# obc.net
KiCad netlist of a schematic drawn in EAGLE
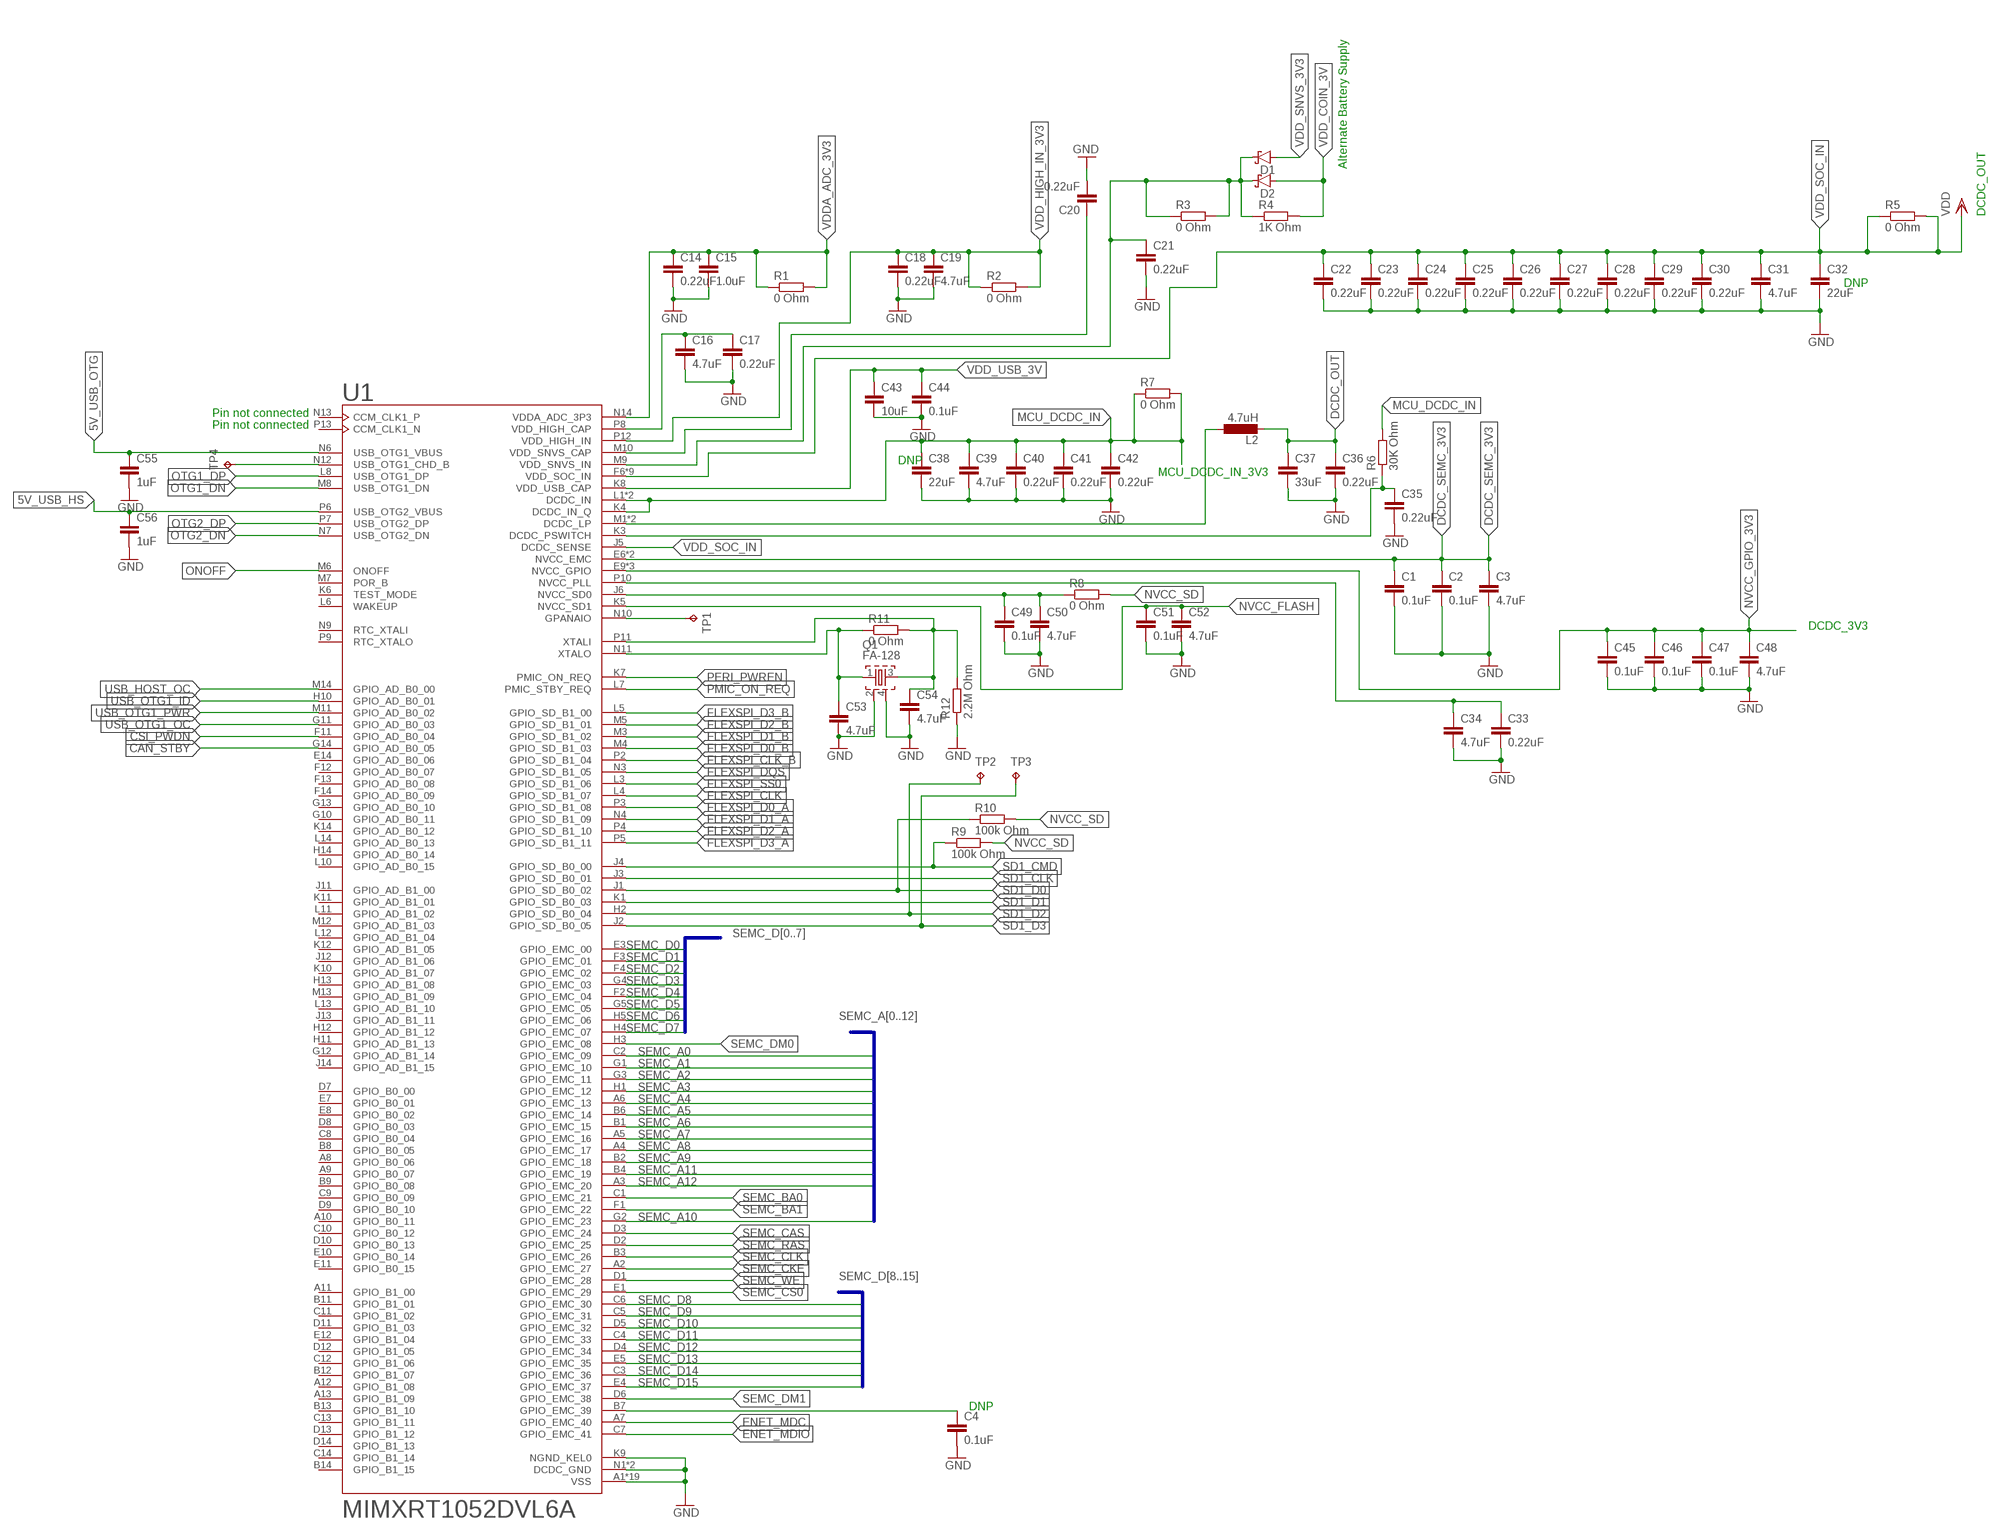
[diagram p0: schematic, sheet 1]
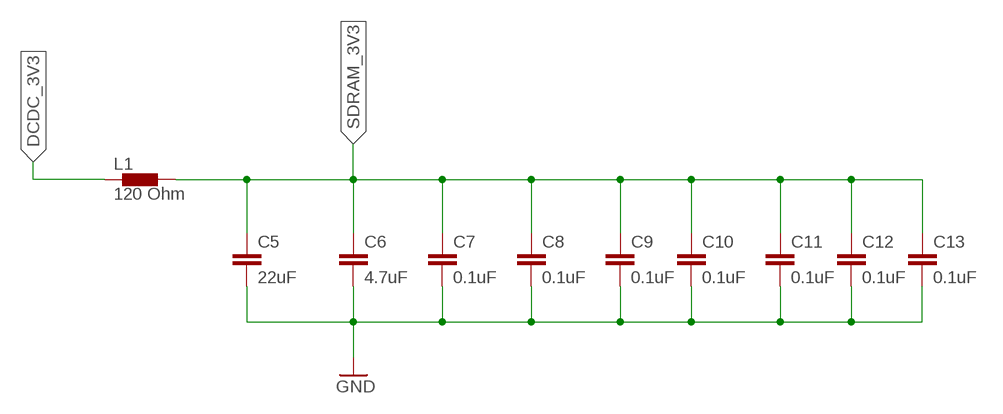
[diagram p1: schematic, sheet 2]

(export (version "E")
  (design (tool "Eeschema 10.0.6"))
  (components
    (comp (ref "C5")
      (value "22uF")
      (footprint "eagle-import:C0402K")
      (libsource (lib "eagle-import") (part "C-EUC0402K"))
    )
    (comp (ref "C6")
      (value "4.7uF")
      (footprint "eagle-import:C0402K")
      (libsource (lib "eagle-import") (part "C-EUC0402K"))
    )
    (comp (ref "C7")
      (value "0.1uF")
      (footprint "eagle-import:C0402K")
      (libsource (lib "eagle-import") (part "C-EUC0402K"))
    )
    (comp (ref "C8")
      (value "0.1uF")
      (footprint "eagle-import:C0402K")
      (libsource (lib "eagle-import") (part "C-EUC0402K"))
    )
    (comp (ref "C9")
      (value "0.1uF")
      (footprint "eagle-import:C0402K")
      (libsource (lib "eagle-import") (part "C-EUC0402K"))
    )
    (comp (ref "C10")
      (value "0.1uF")
      (footprint "eagle-import:C0402K")
      (libsource (lib "eagle-import") (part "C-EUC0402K"))
    )
    (comp (ref "C11")
      (value "0.1uF")
      (footprint "eagle-import:C0402K")
      (libsource (lib "eagle-import") (part "C-EUC0402K"))
    )
    (comp (ref "C12")
      (value "0.1uF")
      (footprint "eagle-import:C0402K")
      (libsource (lib "eagle-import") (part "C-EUC0402K"))
    )
    (comp (ref "C13")
      (value "0.1uF")
      (footprint "eagle-import:C0402K")
      (libsource (lib "eagle-import") (part "C-EUC0402K"))
    )
    (comp (ref "L1")
      (value "120 Ohm")
      (footprint "eagle-import:0402")
      (libsource (lib "eagle-import") (part "BLM15HB121SN1"))
    )
    (comp (ref "C1")
      (value "0.1uF")
      (footprint "eagle-import:C0402K")
      (libsource (lib "eagle-import") (part "C-EUC0402K"))
    )
    (comp (ref "C2")
      (value "0.1uF")
      (footprint "eagle-import:C0402K")
      (libsource (lib "eagle-import") (part "C-EUC0402K"))
    )
    (comp (ref "C3")
      (value "4.7uF")
      (footprint "eagle-import:C0402K")
      (libsource (lib "eagle-import") (part "C-EUC0402K"))
    )
    (comp (ref "C4")
      (value "0.1uF")
      (footprint "eagle-import:C0402K")
      (libsource (lib "eagle-import") (part "C-EUC0402K"))
    )
    (comp (ref "C14")
      (value "0.22uF")
      (footprint "eagle-import:C0402K")
      (libsource (lib "eagle-import") (part "C-EUC0402K"))
    )
    (comp (ref "C15")
      (value "1.0uF")
      (footprint "eagle-import:C0402K")
      (libsource (lib "eagle-import") (part "C-EUC0402K"))
    )
    (comp (ref "C16")
      (value "4.7uF")
      (footprint "eagle-import:C0402K")
      (libsource (lib "eagle-import") (part "C-EUC0402K"))
    )
    (comp (ref "C17")
      (value "0.22uF")
      (footprint "eagle-import:C0402K")
      (libsource (lib "eagle-import") (part "C-EUC0402K"))
    )
    (comp (ref "C18")
      (value "0.22uF")
      (footprint "eagle-import:C0402K")
      (libsource (lib "eagle-import") (part "C-EUC0402K"))
    )
    (comp (ref "C19")
      (value "4.7uF")
      (footprint "eagle-import:C0402K")
      (libsource (lib "eagle-import") (part "C-EUC0402K"))
    )
    (comp (ref "C20")
      (value "0.22uF")
      (footprint "eagle-import:C0402K")
      (libsource (lib "eagle-import") (part "C-EUC0402K"))
    )
    (comp (ref "C21")
      (value "0.22uF")
      (footprint "eagle-import:C0402K")
      (libsource (lib "eagle-import") (part "C-EUC0402K"))
    )
    (comp (ref "C22")
      (value "0.22uF")
      (footprint "eagle-import:C0402K")
      (libsource (lib "eagle-import") (part "C-EUC0402K"))
    )
    (comp (ref "C23")
      (value "0.22uF")
      (footprint "eagle-import:C0402K")
      (libsource (lib "eagle-import") (part "C-EUC0402K"))
    )
    (comp (ref "C24")
      (value "0.22uF")
      (footprint "eagle-import:C0402K")
      (libsource (lib "eagle-import") (part "C-EUC0402K"))
    )
    (comp (ref "C25")
      (value "0.22uF")
      (footprint "eagle-import:C0402K")
      (libsource (lib "eagle-import") (part "C-EUC0402K"))
    )
    (comp (ref "C26")
      (value "0.22uF")
      (footprint "eagle-import:C0402K")
      (libsource (lib "eagle-import") (part "C-EUC0402K"))
    )
    (comp (ref "C27")
      (value "0.22uF")
      (footprint "eagle-import:C0402K")
      (libsource (lib "eagle-import") (part "C-EUC0402K"))
    )
    (comp (ref "C28")
      (value "0.22uF")
      (footprint "eagle-import:C0402K")
      (libsource (lib "eagle-import") (part "C-EUC0402K"))
    )
    (comp (ref "C29")
      (value "0.22uF")
      (footprint "eagle-import:C0402K")
      (libsource (lib "eagle-import") (part "C-EUC0402K"))
    )
    (comp (ref "C30")
      (value "0.22uF")
      (footprint "eagle-import:C0402K")
      (libsource (lib "eagle-import") (part "C-EUC0402K"))
    )
    (comp (ref "C31")
      (value "4.7uF")
      (footprint "eagle-import:C0402K")
      (libsource (lib "eagle-import") (part "C-EUC0402K"))
    )
    (comp (ref "C32")
      (value "22uF")
      (footprint "eagle-import:C0603K")
      (libsource (lib "eagle-import") (part "C-EUC0603K"))
    )
    (comp (ref "C33")
      (value "0.22uF")
      (footprint "eagle-import:C0402K")
      (libsource (lib "eagle-import") (part "C-EUC0402K"))
    )
    (comp (ref "C34")
      (value "4.7uF")
      (footprint "eagle-import:C0402K")
      (libsource (lib "eagle-import") (part "C-EUC0402K"))
    )
    (comp (ref "C35")
      (value "0.22uF")
      (footprint "eagle-import:C0402K")
      (libsource (lib "eagle-import") (part "C-EUC0402K"))
    )
    (comp (ref "C36")
      (value "0.22uF")
      (footprint "eagle-import:C0402K")
      (libsource (lib "eagle-import") (part "C-EUC0402K"))
    )
    (comp (ref "C37")
      (value "33uF")
      (footprint "eagle-import:C0402K")
      (libsource (lib "eagle-import") (part "C-EUC0402K"))
    )
    (comp (ref "C38")
      (value "22uF")
      (footprint "eagle-import:C0402K")
      (libsource (lib "eagle-import") (part "C-EUC0402K"))
    )
    (comp (ref "C39")
      (value "4.7uF")
      (footprint "eagle-import:C0402K")
      (libsource (lib "eagle-import") (part "C-EUC0402K"))
    )
    (comp (ref "C40")
      (value "0.22uF")
      (footprint "eagle-import:C0402K")
      (libsource (lib "eagle-import") (part "C-EUC0402K"))
    )
    (comp (ref "C41")
      (value "0.22uF")
      (footprint "eagle-import:C0402K")
      (libsource (lib "eagle-import") (part "C-EUC0402K"))
    )
    (comp (ref "C42")
      (value "0.22uF")
      (footprint "eagle-import:C0402K")
      (libsource (lib "eagle-import") (part "C-EUC0402K"))
    )
    (comp (ref "C43")
      (value "10uF")
      (footprint "eagle-import:C0402K")
      (libsource (lib "eagle-import") (part "C-EUC0402K"))
    )
    (comp (ref "C44")
      (value "0.1uF")
      (footprint "eagle-import:C0402K")
      (libsource (lib "eagle-import") (part "C-EUC0402K"))
    )
    (comp (ref "C45")
      (value "0.1uF")
      (footprint "eagle-import:C0402K")
      (libsource (lib "eagle-import") (part "C-EUC0402K"))
    )
    (comp (ref "C46")
      (value "0.1uF")
      (footprint "eagle-import:C0402K")
      (libsource (lib "eagle-import") (part "C-EUC0402K"))
    )
    (comp (ref "C47")
      (value "0.1uF")
      (footprint "eagle-import:C0402K")
      (libsource (lib "eagle-import") (part "C-EUC0402K"))
    )
    (comp (ref "C48")
      (value "4.7uF")
      (footprint "eagle-import:C0402K")
      (libsource (lib "eagle-import") (part "C-EUC0402K"))
    )
    (comp (ref "C49")
      (value "0.1uF")
      (footprint "eagle-import:C0402K")
      (libsource (lib "eagle-import") (part "C-EUC0402K"))
    )
    (comp (ref "C50")
      (value "4.7uF")
      (footprint "eagle-import:C0402K")
      (libsource (lib "eagle-import") (part "C-EUC0402K"))
    )
    (comp (ref "C51")
      (value "0.1uF")
      (footprint "eagle-import:C0402K")
      (libsource (lib "eagle-import") (part "C-EUC0402K"))
    )
    (comp (ref "C52")
      (value "4.7uF")
      (footprint "eagle-import:C0402K")
      (libsource (lib "eagle-import") (part "C-EUC0402K"))
    )
    (comp (ref "C53")
      (value "4.7uF")
      (footprint "eagle-import:C0402K")
      (libsource (lib "eagle-import") (part "C-EUC0402K"))
    )
    (comp (ref "C54")
      (value "4.7uF")
      (footprint "eagle-import:C0402K")
      (libsource (lib "eagle-import") (part "C-EUC0402K"))
    )
    (comp (ref "C55")
      (value "1uF")
      (footprint "eagle-import:C0402K")
      (libsource (lib "eagle-import") (part "C-EUC0402K"))
    )
    (comp (ref "C56")
      (value "1uF")
      (footprint "eagle-import:C0402K")
      (libsource (lib "eagle-import") (part "C-EUC0402K"))
    )
    (comp (ref "D1")
      (value "SCHOTTKY-DIODESMC")
      (footprint "eagle-import:SMC")
      (libsource (lib "eagle-import") (part "SCHOTTKY-DIODESMC"))
    )
    (comp (ref "D2")
      (value "SCHOTTKY-DIODESMC")
      (footprint "eagle-import:SMC")
      (libsource (lib "eagle-import") (part "SCHOTTKY-DIODESMC"))
    )
    (comp (ref "L2")
      (value "4.7uH")
      (footprint "eagle-import:L4035M")
      (libsource (lib "eagle-import") (part "L-EUL4035M"))
    )
    (comp (ref "Q1")
      (value "FA-128")
      (footprint "eagle-import:FA-128")
      (libsource (lib "eagle-import") (part "FA-128"))
    )
    (comp (ref "R1")
      (value "0 Ohm")
      (footprint "eagle-import:R0402")
      (libsource (lib "eagle-import") (part "R-EU_R0402"))
    )
    (comp (ref "R2")
      (value "0 Ohm")
      (footprint "eagle-import:R0402")
      (libsource (lib "eagle-import") (part "R-EU_R0402"))
    )
    (comp (ref "R3")
      (value "0 Ohm")
      (footprint "eagle-import:R0402")
      (libsource (lib "eagle-import") (part "R-EU_R0402"))
    )
    (comp (ref "R4")
      (value "1K Ohm")
      (footprint "eagle-import:R0402")
      (libsource (lib "eagle-import") (part "R-EU_R0402"))
    )
    (comp (ref "R5")
      (value "0 Ohm")
      (footprint "eagle-import:R0402")
      (libsource (lib "eagle-import") (part "R-EU_R0402"))
    )
    (comp (ref "R6")
      (value "30K Ohm")
      (footprint "eagle-import:R0402")
      (libsource (lib "eagle-import") (part "R-EU_R0402"))
    )
    (comp (ref "R7")
      (value "0 Ohm")
      (footprint "eagle-import:R0402")
      (libsource (lib "eagle-import") (part "R-EU_R0402"))
    )
    (comp (ref "R8")
      (value "0 Ohm")
      (footprint "eagle-import:R0402")
      (libsource (lib "eagle-import") (part "R-EU_R0402"))
    )
    (comp (ref "R9")
      (value "100k Ohm")
      (footprint "eagle-import:R0402")
      (libsource (lib "eagle-import") (part "R-EU_R0402"))
    )
    (comp (ref "R10")
      (value "100k Ohm")
      (footprint "eagle-import:R0402")
      (libsource (lib "eagle-import") (part "R-EU_R0402"))
    )
    (comp (ref "R11")
      (value "0 Ohm")
      (footprint "eagle-import:R0402")
      (libsource (lib "eagle-import") (part "R-EU_R0402"))
    )
    (comp (ref "R12")
      (value "2.2M Ohm")
      (footprint "eagle-import:R0402")
      (libsource (lib "eagle-import") (part "R-EU_R0402"))
    )
    (comp (ref "TP1")
      (value "TPTP06R")
      (footprint "eagle-import:TP06R")
      (libsource (lib "eagle-import") (part "TPTP06R"))
    )
    (comp (ref "TP2")
      (value "TPTP06R")
      (footprint "eagle-import:TP06R")
      (libsource (lib "eagle-import") (part "TPTP06R"))
    )
    (comp (ref "TP3")
      (value "TPTP06R")
      (footprint "eagle-import:TP06R")
      (libsource (lib "eagle-import") (part "TPTP06R"))
    )
    (comp (ref "TP4")
      (value "TPTP06R")
      (footprint "eagle-import:TP06R")
      (libsource (lib "eagle-import") (part "TPTP06R"))
    )
    (comp (ref "U1")
      (value "MIMXRT1052DVL6A")
      (footprint "eagle-import:BGA196C65P14X14_1000X1000X152N")
      (fields (field (name "DIGI-KEY_PART_NUMBER") "568-13515-ND") (field (name "MF") "NXP USA"))
      (libsource (lib "eagle-import") (part "MIMXRT1052DVL6A"))
    )
  )
  (nets
    (net (code "4") (name "5V_USB_HS") (class "Default")
      (node (ref "C56") (pin "1") (pinfunction "1_1") (pintype "passive"))
      (node (ref "U1") (pin "P6") (pinfunction "USB_OTG2_VBUS_P6") (pintype "bidirectional"))
    )
    (net (code "5") (name "5V_USB_OTG") (class "Default")
      (node (ref "C55") (pin "1") (pinfunction "1_1") (pintype "passive"))
      (node (ref "U1") (pin "N6") (pinfunction "USB_OTG1_VBUS_N6") (pintype "bidirectional"))
    )
    (net (code "6") (name "CAN_STBY") (class "Default")
      (node (ref "U1") (pin "G14") (pinfunction "GPIO_AD_B0_05_G14") (pintype "bidirectional"))
    )
    (net (code "7") (name "CSI_PWDN") (class "Default")
      (node (ref "U1") (pin "F11") (pinfunction "GPIO_AD_B0_04_F11") (pintype "bidirectional"))
    )
    (net (code "8") (name "DCDC_3V3") (class "Default")
      (node (ref "L1") (pin "1") (pinfunction "1_1") (pintype "passive"))
    )
    (net (code "9") (name "DCDC_OUT") (class "Default")
      (node (ref "C36") (pin "1") (pinfunction "1_1") (pintype "passive"))
      (node (ref "C37") (pin "1") (pinfunction "1_1") (pintype "passive"))
      (node (ref "L2") (pin "2") (pinfunction "2_2") (pintype "passive"))
    )
    (net (code "10") (name "DCDC_SEMC_3V3") (class "Default")
      (node (ref "C1") (pin "1") (pinfunction "1_1") (pintype "passive"))
      (node (ref "C2") (pin "1") (pinfunction "1_1") (pintype "passive"))
      (node (ref "C3") (pin "1") (pinfunction "1_1") (pintype "passive"))
      (node (ref "U1") (pin "E6") (pinfunction "NVCC_EMC_E6") (pintype "power_in"))
      (node (ref "U1") (pin "F5") (pinfunction "NVCC_EMC_F5") (pintype "power_in"))
    )
    (net (code "11") (name "ENET_MDC") (class "Default")
      (node (ref "U1") (pin "A7") (pinfunction "GPIO_EMC_40_A7") (pintype "bidirectional"))
    )
    (net (code "12") (name "ENET_MDIO") (class "Default")
      (node (ref "U1") (pin "C7") (pinfunction "GPIO_EMC_41_C7") (pintype "bidirectional"))
    )
    (net (code "13") (name "FLEXSPI_CLK") (class "Default")
      (node (ref "U1") (pin "L4") (pinfunction "GPIO_SD_B1_07_L4") (pintype "bidirectional"))
    )
    (net (code "14") (name "FLEXSPI_CLK_B") (class "Default")
      (node (ref "U1") (pin "P2") (pinfunction "GPIO_SD_B1_04_P2") (pintype "bidirectional"))
    )
    (net (code "15") (name "FLEXSPI_D0_A") (class "Default")
      (node (ref "U1") (pin "P3") (pinfunction "GPIO_SD_B1_08_P3") (pintype "bidirectional"))
    )
    (net (code "16") (name "FLEXSPI_D0_B") (class "Default")
      (node (ref "U1") (pin "M4") (pinfunction "GPIO_SD_B1_03_M4") (pintype "bidirectional"))
    )
    (net (code "17") (name "FLEXSPI_D1_A") (class "Default")
      (node (ref "U1") (pin "N4") (pinfunction "GPIO_SD_B1_09_N4") (pintype "bidirectional"))
    )
    (net (code "18") (name "FLEXSPI_D1_B") (class "Default")
      (node (ref "U1") (pin "M3") (pinfunction "GPIO_SD_B1_02_M3") (pintype "bidirectional"))
    )
    (net (code "19") (name "FLEXSPI_D2_A") (class "Default")
      (node (ref "U1") (pin "P4") (pinfunction "GPIO_SD_B1_10_P4") (pintype "bidirectional"))
    )
    (net (code "20") (name "FLEXSPI_D2_B") (class "Default")
      (node (ref "U1") (pin "M5") (pinfunction "GPIO_SD_B1_01_M5") (pintype "bidirectional"))
    )
    (net (code "21") (name "FLEXSPI_D3_A") (class "Default")
      (node (ref "U1") (pin "P5") (pinfunction "GPIO_SD_B1_11_P5") (pintype "bidirectional"))
    )
    (net (code "22") (name "FLEXSPI_D3_B") (class "Default")
      (node (ref "U1") (pin "L5") (pinfunction "GPIO_SD_B1_00_L5") (pintype "bidirectional"))
    )
    (net (code "23") (name "FLEXSPI_DQS") (class "Default")
      (node (ref "U1") (pin "N3") (pinfunction "GPIO_SD_B1_05_N3") (pintype "bidirectional"))
    )
    (net (code "24") (name "FLEXSPI_SS0") (class "Default")
      (node (ref "U1") (pin "L3") (pinfunction "GPIO_SD_B1_06_L3") (pintype "bidirectional"))
    )
    (net (code "25") (name "GND") (class "Default")
      (node (ref "C1") (pin "2") (pinfunction "2_2") (pintype "passive"))
      (node (ref "C10") (pin "2") (pinfunction "2_2") (pintype "passive"))
      (node (ref "C11") (pin "2") (pinfunction "2_2") (pintype "passive"))
      (node (ref "C12") (pin "2") (pinfunction "2_2") (pintype "passive"))
      (node (ref "C13") (pin "2") (pinfunction "2_2") (pintype "passive"))
      (node (ref "C14") (pin "2") (pinfunction "2_2") (pintype "passive"))
      (node (ref "C15") (pin "2") (pinfunction "2_2") (pintype "passive"))
      (node (ref "C16") (pin "2") (pinfunction "2_2") (pintype "passive"))
      (node (ref "C17") (pin "2") (pinfunction "2_2") (pintype "passive"))
      (node (ref "C18") (pin "2") (pinfunction "2_2") (pintype "passive"))
      (node (ref "C19") (pin "2") (pinfunction "2_2") (pintype "passive"))
      (node (ref "C2") (pin "2") (pinfunction "2_2") (pintype "passive"))
      (node (ref "C20") (pin "2") (pinfunction "2_2") (pintype "passive"))
      (node (ref "C21") (pin "2") (pinfunction "2_2") (pintype "passive"))
      (node (ref "C22") (pin "2") (pinfunction "2_2") (pintype "passive"))
      (node (ref "C23") (pin "2") (pinfunction "2_2") (pintype "passive"))
      (node (ref "C24") (pin "2") (pinfunction "2_2") (pintype "passive"))
      (node (ref "C25") (pin "2") (pinfunction "2_2") (pintype "passive"))
      (node (ref "C26") (pin "2") (pinfunction "2_2") (pintype "passive"))
      (node (ref "C27") (pin "2") (pinfunction "2_2") (pintype "passive"))
      (node (ref "C28") (pin "2") (pinfunction "2_2") (pintype "passive"))
      (node (ref "C29") (pin "2") (pinfunction "2_2") (pintype "passive"))
      (node (ref "C3") (pin "2") (pinfunction "2_2") (pintype "passive"))
      (node (ref "C30") (pin "2") (pinfunction "2_2") (pintype "passive"))
      (node (ref "C31") (pin "2") (pinfunction "2_2") (pintype "passive"))
      (node (ref "C32") (pin "2") (pinfunction "2_2") (pintype "passive"))
      (node (ref "C33") (pin "2") (pinfunction "2_2") (pintype "passive"))
      (node (ref "C34") (pin "2") (pinfunction "2_2") (pintype "passive"))
      (node (ref "C35") (pin "2") (pinfunction "2_2") (pintype "passive"))
      (node (ref "C36") (pin "2") (pinfunction "2_2") (pintype "passive"))
      (node (ref "C37") (pin "2") (pinfunction "2_2") (pintype "passive"))
      (node (ref "C38") (pin "2") (pinfunction "2_2") (pintype "passive"))
      (node (ref "C39") (pin "2") (pinfunction "2_2") (pintype "passive"))
      (node (ref "C4") (pin "2") (pinfunction "2_2") (pintype "passive"))
      (node (ref "C40") (pin "2") (pinfunction "2_2") (pintype "passive"))
      (node (ref "C41") (pin "2") (pinfunction "2_2") (pintype "passive"))
      (node (ref "C42") (pin "2") (pinfunction "2_2") (pintype "passive"))
      (node (ref "C43") (pin "2") (pinfunction "2_2") (pintype "passive"))
      (node (ref "C44") (pin "2") (pinfunction "2_2") (pintype "passive"))
      (node (ref "C45") (pin "2") (pinfunction "2_2") (pintype "passive"))
      (node (ref "C46") (pin "2") (pinfunction "2_2") (pintype "passive"))
      (node (ref "C47") (pin "2") (pinfunction "2_2") (pintype "passive"))
      (node (ref "C48") (pin "2") (pinfunction "2_2") (pintype "passive"))
      (node (ref "C49") (pin "2") (pinfunction "2_2") (pintype "passive"))
      (node (ref "C5") (pin "2") (pinfunction "2_2") (pintype "passive"))
      (node (ref "C50") (pin "2") (pinfunction "2_2") (pintype "passive"))
      (node (ref "C51") (pin "2") (pinfunction "2_2") (pintype "passive"))
      (node (ref "C52") (pin "2") (pinfunction "2_2") (pintype "passive"))
      (node (ref "C53") (pin "2") (pinfunction "2_2") (pintype "passive"))
      (node (ref "C54") (pin "2") (pinfunction "2_2") (pintype "passive"))
      (node (ref "C55") (pin "2") (pinfunction "2_2") (pintype "passive"))
      (node (ref "C56") (pin "2") (pinfunction "2_2") (pintype "passive"))
      (node (ref "C6") (pin "2") (pinfunction "2_2") (pintype "passive"))
      (node (ref "C7") (pin "2") (pinfunction "2_2") (pintype "passive"))
      (node (ref "C8") (pin "2") (pinfunction "2_2") (pintype "passive"))
      (node (ref "C9") (pin "2") (pinfunction "2_2") (pintype "passive"))
      (node (ref "Q1") (pin "2") (pinfunction "2_2") (pintype "passive"))
      (node (ref "Q1") (pin "4") (pinfunction "4_4") (pintype "passive"))
      (node (ref "R12") (pin "1") (pinfunction "1_1") (pintype "passive"))
      (node (ref "U1") (pin "A1") (pinfunction "VSS_A1") (pintype "power_in"))
      (node (ref "U1") (pin "A14") (pinfunction "VSS_A14") (pintype "power_in"))
      (node (ref "U1") (pin "B10") (pinfunction "VSS_B10") (pintype "power_in"))
      (node (ref "U1") (pin "B5") (pinfunction "VSS_B5") (pintype "power_in"))
      (node (ref "U1") (pin "E13") (pinfunction "VSS_E13") (pintype "power_in"))
      (node (ref "U1") (pin "E2") (pinfunction "VSS_E2") (pintype "power_in"))
      (node (ref "U1") (pin "G7") (pinfunction "VSS_G7") (pintype "power_in"))
      (node (ref "U1") (pin "G8") (pinfunction "VSS_G8") (pintype "power_in"))
      (node (ref "U1") (pin "H7") (pinfunction "VSS_H7") (pintype "power_in"))
      (node (ref "U1") (pin "H8") (pinfunction "VSS_H8") (pintype "power_in"))
      (node (ref "U1") (pin "J7") (pinfunction "VSS_J7") (pintype "power_in"))
      (node (ref "U1") (pin "J8") (pinfunction "VSS_J8") (pintype "power_in"))
      (node (ref "U1") (pin "K13") (pinfunction "VSS_K13") (pintype "power_in"))
      (node (ref "U1") (pin "K2") (pinfunction "VSS_K2") (pintype "power_in"))
      (node (ref "U1") (pin "K9") (pinfunction "NGND_KEL0_K9") (pintype "power_in"))
      (node (ref "U1") (pin "L9") (pinfunction "VSS_L9") (pintype "power_in"))
      (node (ref "U1") (pin "N1") (pinfunction "DCDC_GND_N1") (pintype "power_in"))
      (node (ref "U1") (pin "N2") (pinfunction "DCDC_GND_N2") (pintype "power_in"))
      (node (ref "U1") (pin "N5") (pinfunction "VSS_N5") (pintype "power_in"))
      (node (ref "U1") (pin "N8") (pinfunction "VSS_N8") (pintype "power_in"))
      (node (ref "U1") (pin "P1") (pinfunction "VSS_P1") (pintype "power_in"))
      (node (ref "U1") (pin "P14") (pinfunction "VSS_P14") (pintype "power_in"))
    )
    (net (code "26") (name "MCU_DCDC_IN") (class "Default")
      (node (ref "C38") (pin "1") (pinfunction "1_1") (pintype "passive"))
      (node (ref "C39") (pin "1") (pinfunction "1_1") (pintype "passive"))
      (node (ref "C40") (pin "1") (pinfunction "1_1") (pintype "passive"))
      (node (ref "C41") (pin "1") (pinfunction "1_1") (pintype "passive"))
      (node (ref "C42") (pin "1") (pinfunction "1_1") (pintype "passive"))
      (node (ref "R6") (pin "2") (pinfunction "2_2") (pintype "passive"))
      (node (ref "R7") (pin "1") (pinfunction "1_1") (pintype "passive"))
      (node (ref "R7") (pin "2") (pinfunction "2_2") (pintype "passive"))
      (node (ref "U1") (pin "K4") (pinfunction "DCDC_IN_Q_K4") (pintype "power_in"))
      (node (ref "U1") (pin "L1") (pinfunction "DCDC_IN_L1") (pintype "power_in"))
      (node (ref "U1") (pin "L2") (pinfunction "DCDC_IN_L2") (pintype "power_in"))
    )
    (net (code "27") (name "NVCC_FLASH") (class "Default")
      (node (ref "C51") (pin "1") (pinfunction "1_1") (pintype "passive"))
      (node (ref "C52") (pin "1") (pinfunction "1_1") (pintype "passive"))
      (node (ref "U1") (pin "K5") (pinfunction "NVCC_SD1_K5") (pintype "power_in"))
    )
    (net (code "28") (name "NVCC_GPIO_3V3") (class "Default")
      (node (ref "C45") (pin "1") (pinfunction "1_1") (pintype "passive"))
      (node (ref "C46") (pin "1") (pinfunction "1_1") (pintype "passive"))
      (node (ref "C47") (pin "1") (pinfunction "1_1") (pintype "passive"))
      (node (ref "C48") (pin "1") (pinfunction "1_1") (pintype "passive"))
      (node (ref "U1") (pin "E9") (pinfunction "NVCC_GPIO_E9") (pintype "power_in"))
      (node (ref "U1") (pin "F10") (pinfunction "NVCC_GPIO_F10") (pintype "power_in"))
      (node (ref "U1") (pin "J10") (pinfunction "NVCC_GPIO_J10") (pintype "power_in"))
    )
    (net (code "29") (name "NVCC_SD") (class "Default")
      (node (ref "R10") (pin "2") (pinfunction "2_2") (pintype "passive"))
      (node (ref "R8") (pin "2") (pinfunction "2_2") (pintype "passive"))
      (node (ref "R9") (pin "2") (pinfunction "2_2") (pintype "passive"))
    )
    (net (code "30") (name "Net-(L2-Pad1)") (class "Default")
      (node (ref "L2") (pin "1") (pinfunction "1_1") (pintype "passive"))
      (node (ref "U1") (pin "M1") (pinfunction "DCDC_LP_M1") (pintype "power_in"))
      (node (ref "U1") (pin "M2") (pinfunction "DCDC_LP_M2") (pintype "power_in"))
    )
    (net (code "31") (name "Net-(U1-DCDC_PSWITCH)") (class "Default")
      (node (ref "C35") (pin "1") (pinfunction "1_1") (pintype "passive"))
      (node (ref "R6") (pin "1") (pinfunction "1_1") (pintype "passive"))
      (node (ref "U1") (pin "K3") (pinfunction "DCDC_PSWITCH_K3") (pintype "power_in"))
    )
    (net (code "32") (name "Net-(U1-GPANAIO)") (class "Default")
      (node (ref "TP1") (pin "TP") (pinfunction "TP_TP") (pintype "input"))
      (node (ref "U1") (pin "N10") (pinfunction "GPANAIO_N10") (pintype "power_in"))
    )
    (net (code "33") (name "Net-(U1-GPIO_EMC_39)") (class "Default")
      (node (ref "C4") (pin "1") (pinfunction "1_1") (pintype "passive"))
      (node (ref "U1") (pin "B7") (pinfunction "GPIO_EMC_39_B7") (pintype "bidirectional"))
    )
    (net (code "34") (name "Net-(U1-NVCC_PLL)") (class "Default")
      (node (ref "C33") (pin "1") (pinfunction "1_1") (pintype "passive"))
      (node (ref "C34") (pin "1") (pinfunction "1_1") (pintype "passive"))
      (node (ref "U1") (pin "P10") (pinfunction "NVCC_PLL_P10") (pintype "power_in"))
    )
    (net (code "35") (name "Net-(U1-NVCC_SD0)") (class "Default")
      (node (ref "C49") (pin "1") (pinfunction "1_1") (pintype "passive"))
      (node (ref "C50") (pin "1") (pinfunction "1_1") (pintype "passive"))
      (node (ref "R8") (pin "1") (pinfunction "1_1") (pintype "passive"))
      (node (ref "U1") (pin "J6") (pinfunction "NVCC_SD0_J6") (pintype "power_in"))
    )
    (net (code "36") (name "Net-(U1-USB_OTG1_CHD_B)") (class "Default")
      (node (ref "TP4") (pin "TP") (pinfunction "TP_TP") (pintype "input"))
      (node (ref "U1") (pin "N12") (pinfunction "USB_OTG1_CHD_B_N12") (pintype "bidirectional"))
    )
    (net (code "37") (name "Net-(U1-VDD_HIGH_CAP)") (class "Default")
      (node (ref "C16") (pin "1") (pinfunction "1_1") (pintype "passive"))
      (node (ref "C17") (pin "1") (pinfunction "1_1") (pintype "passive"))
      (node (ref "U1") (pin "P8") (pinfunction "VDD_HIGH_CAP_P8") (pintype "power_in"))
    )
    (net (code "38") (name "Net-(U1-VDD_SNVS_CAP)") (class "Default")
      (node (ref "C20") (pin "1") (pinfunction "1_1") (pintype "passive"))
      (node (ref "U1") (pin "M10") (pinfunction "VDD_SNVS_CAP_M10") (pintype "power_in"))
    )
    (net (code "39") (name "Net-(U1-VDD_SNVS_IN)") (class "Default")
      (node (ref "C21") (pin "1") (pinfunction "1_1") (pintype "passive"))
      (node (ref "D1") (pin "C") (pinfunction "C_C") (pintype "passive"))
      (node (ref "D2") (pin "C") (pinfunction "C_C") (pintype "passive"))
      (node (ref "R3") (pin "1") (pinfunction "1_1") (pintype "passive"))
      (node (ref "R3") (pin "2") (pinfunction "2_2") (pintype "passive"))
      (node (ref "R4") (pin "1") (pinfunction "1_1") (pintype "passive"))
      (node (ref "U1") (pin "M9") (pinfunction "VDD_SNVS_IN_M9") (pintype "power_in"))
    )
    (net (code "40") (name "Net-(U1-XTALI)") (class "Default")
      (node (ref "C54") (pin "1") (pinfunction "1_1") (pintype "passive"))
      (node (ref "Q1") (pin "3") (pinfunction "3_3") (pintype "passive"))
      (node (ref "R11") (pin "2") (pinfunction "2_2") (pintype "passive"))
      (node (ref "R12") (pin "2") (pinfunction "2_2") (pintype "passive"))
      (node (ref "U1") (pin "P11") (pinfunction "XTALI_P11") (pintype "input"))
    )
    (net (code "41") (name "Net-(U1-XTALO)") (class "Default")
      (node (ref "C53") (pin "1") (pinfunction "1_1") (pintype "passive"))
      (node (ref "Q1") (pin "1") (pinfunction "1_1") (pintype "passive"))
      (node (ref "R11") (pin "1") (pinfunction "1_1") (pintype "passive"))
      (node (ref "U1") (pin "N11") (pinfunction "XTALO_N11") (pintype "output"))
    )
    (net (code "42") (name "ONOFF") (class "Default")
      (node (ref "U1") (pin "M6") (pinfunction "ONOFF_M6") (pintype "input"))
    )
    (net (code "43") (name "OTG1_DN") (class "Default")
      (node (ref "U1") (pin "M8") (pinfunction "USB_OTG1_DN_M8") (pintype "bidirectional"))
    )
    (net (code "44") (name "OTG1_DP") (class "Default")
      (node (ref "U1") (pin "L8") (pinfunction "USB_OTG1_DP_L8") (pintype "bidirectional"))
    )
    (net (code "45") (name "OTG2_DN") (class "Default")
      (node (ref "U1") (pin "N7") (pinfunction "USB_OTG2_DN_N7") (pintype "bidirectional"))
    )
    (net (code "46") (name "OTG2_DP") (class "Default")
      (node (ref "U1") (pin "P7") (pinfunction "USB_OTG2_DP_P7") (pintype "bidirectional"))
    )
    (net (code "47") (name "PERI_PWREN") (class "Default")
      (node (ref "U1") (pin "K7") (pinfunction "PMIC_ON_REQ_K7") (pintype "output"))
    )
    (net (code "48") (name "PMIC_ON_REQ") (class "Default")
      (node (ref "U1") (pin "L7") (pinfunction "PMIC_STBY_REQ_L7") (pintype "output"))
    )
    (net (code "49") (name "SD1_CLK") (class "Default")
      (node (ref "U1") (pin "J3") (pinfunction "GPIO_SD_B0_01_J3") (pintype "bidirectional"))
    )
    (net (code "50") (name "SD1_CMD") (class "Default")
      (node (ref "R9") (pin "1") (pinfunction "1_1") (pintype "passive"))
      (node (ref "U1") (pin "J4") (pinfunction "GPIO_SD_B0_00_J4") (pintype "bidirectional"))
    )
    (net (code "51") (name "SD1_D0") (class "Default")
      (node (ref "R10") (pin "1") (pinfunction "1_1") (pintype "passive"))
      (node (ref "U1") (pin "J1") (pinfunction "GPIO_SD_B0_02_J1") (pintype "bidirectional"))
    )
    (net (code "52") (name "SD1_D1") (class "Default")
      (node (ref "U1") (pin "K1") (pinfunction "GPIO_SD_B0_03_K1") (pintype "bidirectional"))
    )
    (net (code "53") (name "SD1_D2") (class "Default")
      (node (ref "TP2") (pin "TP") (pinfunction "TP_TP") (pintype "input"))
      (node (ref "U1") (pin "H2") (pinfunction "GPIO_SD_B0_04_H2") (pintype "bidirectional"))
    )
    (net (code "54") (name "SD1_D3") (class "Default")
      (node (ref "TP3") (pin "TP") (pinfunction "TP_TP") (pintype "input"))
      (node (ref "U1") (pin "J2") (pinfunction "GPIO_SD_B0_05_J2") (pintype "bidirectional"))
    )
    (net (code "55") (name "SDRAM_3V3") (class "Default")
      (node (ref "C10") (pin "1") (pinfunction "1_1") (pintype "passive"))
      (node (ref "C11") (pin "1") (pinfunction "1_1") (pintype "passive"))
      (node (ref "C12") (pin "1") (pinfunction "1_1") (pintype "passive"))
      (node (ref "C13") (pin "1") (pinfunction "1_1") (pintype "passive"))
      (node (ref "C5") (pin "1") (pinfunction "1_1") (pintype "passive"))
      (node (ref "C6") (pin "1") (pinfunction "1_1") (pintype "passive"))
      (node (ref "C7") (pin "1") (pinfunction "1_1") (pintype "passive"))
      (node (ref "C8") (pin "1") (pinfunction "1_1") (pintype "passive"))
      (node (ref "C9") (pin "1") (pinfunction "1_1") (pintype "passive"))
      (node (ref "L1") (pin "2") (pinfunction "2_2") (pintype "passive"))
    )
    (net (code "56") (name "SEMC_A0") (class "Default")
      (node (ref "U1") (pin "C2") (pinfunction "GPIO_EMC_09_C2") (pintype "bidirectional"))
    )
    (net (code "57") (name "SEMC_A1") (class "Default")
      (node (ref "U1") (pin "G1") (pinfunction "GPIO_EMC_10_G1") (pintype "bidirectional"))
    )
    (net (code "58") (name "SEMC_A2") (class "Default")
      (node (ref "U1") (pin "G3") (pinfunction "GPIO_EMC_11_G3") (pintype "bidirectional"))
    )
    (net (code "59") (name "SEMC_A3") (class "Default")
      (node (ref "U1") (pin "H1") (pinfunction "GPIO_EMC_12_H1") (pintype "bidirectional"))
    )
    (net (code "60") (name "SEMC_A4") (class "Default")
      (node (ref "U1") (pin "A6") (pinfunction "GPIO_EMC_13_A6") (pintype "bidirectional"))
    )
    (net (code "61") (name "SEMC_A5") (class "Default")
      (node (ref "U1") (pin "B6") (pinfunction "GPIO_EMC_14_B6") (pintype "bidirectional"))
    )
    (net (code "62") (name "SEMC_A6") (class "Default")
      (node (ref "U1") (pin "B1") (pinfunction "GPIO_EMC_15_B1") (pintype "bidirectional"))
    )
    (net (code "63") (name "SEMC_A7") (class "Default")
      (node (ref "U1") (pin "A5") (pinfunction "GPIO_EMC_16_A5") (pintype "bidirectional"))
    )
    (net (code "64") (name "SEMC_A8") (class "Default")
      (node (ref "U1") (pin "A4") (pinfunction "GPIO_EMC_17_A4") (pintype "bidirectional"))
    )
    (net (code "65") (name "SEMC_A9") (class "Default")
      (node (ref "U1") (pin "B2") (pinfunction "GPIO_EMC_18_B2") (pintype "bidirectional"))
    )
    (net (code "66") (name "SEMC_A10") (class "Default")
      (node (ref "U1") (pin "G2") (pinfunction "GPIO_EMC_23_G2") (pintype "bidirectional"))
    )
    (net (code "67") (name "SEMC_A11") (class "Default")
      (node (ref "U1") (pin "B4") (pinfunction "GPIO_EMC_19_B4") (pintype "bidirectional"))
    )
    (net (code "68") (name "SEMC_A12") (class "Default")
      (node (ref "U1") (pin "A3") (pinfunction "GPIO_EMC_20_A3") (pintype "bidirectional"))
    )
    (net (code "69") (name "SEMC_BA0") (class "Default")
      (node (ref "U1") (pin "C1") (pinfunction "GPIO_EMC_21_C1") (pintype "bidirectional"))
    )
    (net (code "70") (name "SEMC_BA1") (class "Default")
      (node (ref "U1") (pin "F1") (pinfunction "GPIO_EMC_22_F1") (pintype "bidirectional"))
    )
    (net (code "71") (name "SEMC_CAS") (class "Default")
      (node (ref "U1") (pin "D3") (pinfunction "GPIO_EMC_24_D3") (pintype "bidirectional"))
    )
    (net (code "72") (name "SEMC_CKE") (class "Default")
      (node (ref "U1") (pin "A2") (pinfunction "GPIO_EMC_27_A2") (pintype "bidirectional"))
    )
    (net (code "73") (name "SEMC_CLK") (class "Default")
      (node (ref "U1") (pin "B3") (pinfunction "GPIO_EMC_26_B3") (pintype "bidirectional"))
    )
    (net (code "74") (name "SEMC_CS0") (class "Default")
      (node (ref "U1") (pin "E1") (pinfunction "GPIO_EMC_29_E1") (pintype "bidirectional"))
    )
    (net (code "75") (name "SEMC_D0") (class "Default")
      (node (ref "U1") (pin "E3") (pinfunction "GPIO_EMC_00_E3") (pintype "bidirectional"))
    )
    (net (code "76") (name "SEMC_D1") (class "Default")
      (node (ref "U1") (pin "F3") (pinfunction "GPIO_EMC_01_F3") (pintype "bidirectional"))
    )
    (net (code "77") (name "SEMC_D2") (class "Default")
      (node (ref "U1") (pin "F4") (pinfunction "GPIO_EMC_02_F4") (pintype "bidirectional"))
    )
    (net (code "78") (name "SEMC_D3") (class "Default")
      (node (ref "U1") (pin "G4") (pinfunction "GPIO_EMC_03_G4") (pintype "bidirectional"))
    )
    (net (code "79") (name "SEMC_D4") (class "Default")
      (node (ref "U1") (pin "F2") (pinfunction "GPIO_EMC_04_F2") (pintype "bidirectional"))
    )
    (net (code "80") (name "SEMC_D5") (class "Default")
      (node (ref "U1") (pin "G5") (pinfunction "GPIO_EMC_05_G5") (pintype "bidirectional"))
    )
    (net (code "81") (name "SEMC_D6") (class "Default")
      (node (ref "U1") (pin "H5") (pinfunction "GPIO_EMC_06_H5") (pintype "bidirectional"))
    )
    (net (code "82") (name "SEMC_D7") (class "Default")
      (node (ref "U1") (pin "H4") (pinfunction "GPIO_EMC_07_H4") (pintype "bidirectional"))
    )
    (net (code "83") (name "SEMC_D8") (class "Default")
      (node (ref "U1") (pin "C6") (pinfunction "GPIO_EMC_30_C6") (pintype "bidirectional"))
    )
    (net (code "84") (name "SEMC_D9") (class "Default")
      (node (ref "U1") (pin "C5") (pinfunction "GPIO_EMC_31_C5") (pintype "bidirectional"))
    )
    (net (code "85") (name "SEMC_D10") (class "Default")
      (node (ref "U1") (pin "D5") (pinfunction "GPIO_EMC_32_D5") (pintype "bidirectional"))
    )
    (net (code "86") (name "SEMC_D11") (class "Default")
      (node (ref "U1") (pin "C4") (pinfunction "GPIO_EMC_33_C4") (pintype "bidirectional"))
    )
    (net (code "87") (name "SEMC_D12") (class "Default")
      (node (ref "U1") (pin "D4") (pinfunction "GPIO_EMC_34_D4") (pintype "bidirectional"))
    )
    (net (code "88") (name "SEMC_D13") (class "Default")
      (node (ref "U1") (pin "E5") (pinfunction "GPIO_EMC_35_E5") (pintype "bidirectional"))
    )
    (net (code "89") (name "SEMC_D14") (class "Default")
      (node (ref "U1") (pin "C3") (pinfunction "GPIO_EMC_36_C3") (pintype "bidirectional"))
    )
    (net (code "90") (name "SEMC_D15") (class "Default")
      (node (ref "U1") (pin "E4") (pinfunction "GPIO_EMC_37_E4") (pintype "bidirectional"))
    )
    (net (code "91") (name "SEMC_DM0") (class "Default")
      (node (ref "U1") (pin "H3") (pinfunction "GPIO_EMC_08_H3") (pintype "bidirectional"))
    )
    (net (code "92") (name "SEMC_DM1") (class "Default")
      (node (ref "U1") (pin "D6") (pinfunction "GPIO_EMC_38_D6") (pintype "bidirectional"))
    )
    (net (code "93") (name "SEMC_RAS") (class "Default")
      (node (ref "U1") (pin "D2") (pinfunction "GPIO_EMC_25_D2") (pintype "bidirectional"))
    )
    (net (code "94") (name "SEMC_WE") (class "Default")
      (node (ref "U1") (pin "D1") (pinfunction "GPIO_EMC_28_D1") (pintype "bidirectional"))
    )
    (net (code "95") (name "USB_HOST_OC") (class "Default")
      (node (ref "U1") (pin "M14") (pinfunction "GPIO_AD_B0_00_M14") (pintype "bidirectional"))
    )
    (net (code "96") (name "USB_OTG1_ID") (class "Default")
      (node (ref "U1") (pin "H10") (pinfunction "GPIO_AD_B0_01_H10") (pintype "bidirectional"))
    )
    (net (code "97") (name "USB_OTG1_OC") (class "Default")
      (node (ref "U1") (pin "G11") (pinfunction "GPIO_AD_B0_03_G11") (pintype "bidirectional"))
    )
    (net (code "98") (name "USB_OTG1_PWR") (class "Default")
      (node (ref "U1") (pin "M11") (pinfunction "GPIO_AD_B0_02_M11") (pintype "bidirectional"))
    )
    (net (code "99") (name "VDDA_ADC_3V3") (class "Default")
      (node (ref "C14") (pin "1") (pinfunction "1_1") (pintype "passive"))
      (node (ref "C15") (pin "1") (pinfunction "1_1") (pintype "passive"))
      (node (ref "R1") (pin "1") (pinfunction "1_1") (pintype "passive"))
      (node (ref "R1") (pin "2") (pinfunction "2_2") (pintype "passive"))
      (node (ref "U1") (pin "N14") (pinfunction "VDDA_ADC_3P3_N14") (pintype "power_in"))
    )
    (net (code "100") (name "VDD_COIN_3V") (class "Default")
      (node (ref "D2") (pin "A") (pinfunction "A_A") (pintype "passive"))
      (node (ref "R4") (pin "2") (pinfunction "2_2") (pintype "passive"))
    )
    (net (code "101") (name "VDD_HIGH_IN_3V3") (class "Default")
      (node (ref "C18") (pin "1") (pinfunction "1_1") (pintype "passive"))
      (node (ref "C19") (pin "1") (pinfunction "1_1") (pintype "passive"))
      (node (ref "R2") (pin "1") (pinfunction "1_1") (pintype "passive"))
      (node (ref "R2") (pin "2") (pinfunction "2_2") (pintype "passive"))
      (node (ref "U1") (pin "P12") (pinfunction "VDD_HIGH_IN_P12") (pintype "power_in"))
    )
    (net (code "102") (name "VDD_SNVS_3V3") (class "Default")
      (node (ref "D1") (pin "A") (pinfunction "A_A") (pintype "passive"))
    )
    (net (code "103") (name "VDD_SOC_IN") (class "Default")
      (node (ref "C22") (pin "1") (pinfunction "1_1") (pintype "passive"))
      (node (ref "C23") (pin "1") (pinfunction "1_1") (pintype "passive"))
      (node (ref "C24") (pin "1") (pinfunction "1_1") (pintype "passive"))
      (node (ref "C25") (pin "1") (pinfunction "1_1") (pintype "passive"))
      (node (ref "C26") (pin "1") (pinfunction "1_1") (pintype "passive"))
      (node (ref "C27") (pin "1") (pinfunction "1_1") (pintype "passive"))
      (node (ref "C28") (pin "1") (pinfunction "1_1") (pintype "passive"))
      (node (ref "C29") (pin "1") (pinfunction "1_1") (pintype "passive"))
      (node (ref "C30") (pin "1") (pinfunction "1_1") (pintype "passive"))
      (node (ref "C31") (pin "1") (pinfunction "1_1") (pintype "passive"))
      (node (ref "C32") (pin "1") (pinfunction "1_1") (pintype "passive"))
      (node (ref "R5") (pin "1") (pinfunction "1_1") (pintype "passive"))
      (node (ref "R5") (pin "2") (pinfunction "2_2") (pintype "passive"))
      (node (ref "U1") (pin "F6") (pinfunction "VDD_SOC_IN_F6") (pintype "power_in"))
      (node (ref "U1") (pin "F7") (pinfunction "VDD_SOC_IN_F7") (pintype "power_in"))
      (node (ref "U1") (pin "F8") (pinfunction "VDD_SOC_IN_F8") (pintype "power_in"))
      (node (ref "U1") (pin "F9") (pinfunction "VDD_SOC_IN_F9") (pintype "power_in"))
      (node (ref "U1") (pin "G6") (pinfunction "VDD_SOC_IN_G6") (pintype "power_in"))
      (node (ref "U1") (pin "G9") (pinfunction "VDD_SOC_IN_G9") (pintype "power_in"))
      (node (ref "U1") (pin "H6") (pinfunction "VDD_SOC_IN_H6") (pintype "power_in"))
      (node (ref "U1") (pin "H9") (pinfunction "VDD_SOC_IN_H9") (pintype "power_in"))
      (node (ref "U1") (pin "J5") (pinfunction "DCDC_SENSE_J5") (pintype "power_in"))
      (node (ref "U1") (pin "J9") (pinfunction "VDD_SOC_IN_J9") (pintype "power_in"))
    )
    (net (code "104") (name "VDD_USB_3V") (class "Default")
      (node (ref "C43") (pin "1") (pinfunction "1_1") (pintype "passive"))
      (node (ref "C44") (pin "1") (pinfunction "1_1") (pintype "passive"))
      (node (ref "U1") (pin "K8") (pinfunction "VDD_USB_CAP_K8") (pintype "power_in"))
    )
    (net (code "105") (name "unconnected-(U1-CCM_CLK1_N-PadP13)") (class "Default")
      (node (ref "U1") (pin "P13") (pinfunction "CCM_CLK1_N_P13") (pintype "input"))
    )
    (net (code "106") (name "unconnected-(U1-CCM_CLK1_P-PadN13)") (class "Default")
      (node (ref "U1") (pin "N13") (pinfunction "CCM_CLK1_P_N13") (pintype "input"))
    )
    (net (code "107") (name "unconnected-(U1-GPIO_AD_B0_06-PadE14)") (class "Default")
      (node (ref "U1") (pin "E14") (pinfunction "GPIO_AD_B0_06_E14") (pintype "bidirectional"))
    )
    (net (code "108") (name "unconnected-(U1-GPIO_AD_B0_07-PadF12)") (class "Default")
      (node (ref "U1") (pin "F12") (pinfunction "GPIO_AD_B0_07_F12") (pintype "bidirectional"))
    )
    (net (code "109") (name "unconnected-(U1-GPIO_AD_B0_08-PadF13)") (class "Default")
      (node (ref "U1") (pin "F13") (pinfunction "GPIO_AD_B0_08_F13") (pintype "bidirectional"))
    )
    (net (code "110") (name "unconnected-(U1-GPIO_AD_B0_09-PadF14)") (class "Default")
      (node (ref "U1") (pin "F14") (pinfunction "GPIO_AD_B0_09_F14") (pintype "bidirectional"))
    )
    (net (code "111") (name "unconnected-(U1-GPIO_AD_B0_10-PadG13)") (class "Default")
      (node (ref "U1") (pin "G13") (pinfunction "GPIO_AD_B0_10_G13") (pintype "bidirectional"))
    )
    (net (code "112") (name "unconnected-(U1-GPIO_AD_B0_11-PadG10)") (class "Default")
      (node (ref "U1") (pin "G10") (pinfunction "GPIO_AD_B0_11_G10") (pintype "bidirectional"))
    )
    (net (code "113") (name "unconnected-(U1-GPIO_AD_B0_12-PadK14)") (class "Default")
      (node (ref "U1") (pin "K14") (pinfunction "GPIO_AD_B0_12_K14") (pintype "bidirectional"))
    )
    (net (code "114") (name "unconnected-(U1-GPIO_AD_B0_13-PadL14)") (class "Default")
      (node (ref "U1") (pin "L14") (pinfunction "GPIO_AD_B0_13_L14") (pintype "bidirectional"))
    )
    (net (code "115") (name "unconnected-(U1-GPIO_AD_B0_14-PadH14)") (class "Default")
      (node (ref "U1") (pin "H14") (pinfunction "GPIO_AD_B0_14_H14") (pintype "bidirectional"))
    )
    (net (code "116") (name "unconnected-(U1-GPIO_AD_B0_15-PadL10)") (class "Default")
      (node (ref "U1") (pin "L10") (pinfunction "GPIO_AD_B0_15_L10") (pintype "bidirectional"))
    )
    (net (code "117") (name "unconnected-(U1-GPIO_AD_B1_00-PadJ11)") (class "Default")
      (node (ref "U1") (pin "J11") (pinfunction "GPIO_AD_B1_00_J11") (pintype "bidirectional"))
    )
    (net (code "118") (name "unconnected-(U1-GPIO_AD_B1_01-PadK11)") (class "Default")
      (node (ref "U1") (pin "K11") (pinfunction "GPIO_AD_B1_01_K11") (pintype "bidirectional"))
    )
    (net (code "119") (name "unconnected-(U1-GPIO_AD_B1_02-PadL11)") (class "Default")
      (node (ref "U1") (pin "L11") (pinfunction "GPIO_AD_B1_02_L11") (pintype "bidirectional"))
    )
    (net (code "120") (name "unconnected-(U1-GPIO_AD_B1_03-PadM12)") (class "Default")
      (node (ref "U1") (pin "M12") (pinfunction "GPIO_AD_B1_03_M12") (pintype "bidirectional"))
    )
    (net (code "121") (name "unconnected-(U1-GPIO_AD_B1_04-PadL12)") (class "Default")
      (node (ref "U1") (pin "L12") (pinfunction "GPIO_AD_B1_04_L12") (pintype "bidirectional"))
    )
    (net (code "122") (name "unconnected-(U1-GPIO_AD_B1_05-PadK12)") (class "Default")
      (node (ref "U1") (pin "K12") (pinfunction "GPIO_AD_B1_05_K12") (pintype "bidirectional"))
    )
    (net (code "123") (name "unconnected-(U1-GPIO_AD_B1_06-PadJ12)") (class "Default")
      (node (ref "U1") (pin "J12") (pinfunction "GPIO_AD_B1_06_J12") (pintype "bidirectional"))
    )
    (net (code "124") (name "unconnected-(U1-GPIO_AD_B1_07-PadK10)") (class "Default")
      (node (ref "U1") (pin "K10") (pinfunction "GPIO_AD_B1_07_K10") (pintype "bidirectional"))
    )
    (net (code "125") (name "unconnected-(U1-GPIO_AD_B1_08-PadH13)") (class "Default")
      (node (ref "U1") (pin "H13") (pinfunction "GPIO_AD_B1_08_H13") (pintype "bidirectional"))
    )
    (net (code "126") (name "unconnected-(U1-GPIO_AD_B1_09-PadM13)") (class "Default")
      (node (ref "U1") (pin "M13") (pinfunction "GPIO_AD_B1_09_M13") (pintype "bidirectional"))
    )
    (net (code "127") (name "unconnected-(U1-GPIO_AD_B1_10-PadL13)") (class "Default")
      (node (ref "U1") (pin "L13") (pinfunction "GPIO_AD_B1_10_L13") (pintype "bidirectional"))
    )
    (net (code "128") (name "unconnected-(U1-GPIO_AD_B1_11-PadJ13)") (class "Default")
      (node (ref "U1") (pin "J13") (pinfunction "GPIO_AD_B1_11_J13") (pintype "bidirectional"))
    )
    (net (code "129") (name "unconnected-(U1-GPIO_AD_B1_12-PadH12)") (class "Default")
      (node (ref "U1") (pin "H12") (pinfunction "GPIO_AD_B1_12_H12") (pintype "bidirectional"))
    )
    (net (code "130") (name "unconnected-(U1-GPIO_AD_B1_13-PadH11)") (class "Default")
      (node (ref "U1") (pin "H11") (pinfunction "GPIO_AD_B1_13_H11") (pintype "bidirectional"))
    )
    (net (code "131") (name "unconnected-(U1-GPIO_AD_B1_14-PadG12)") (class "Default")
      (node (ref "U1") (pin "G12") (pinfunction "GPIO_AD_B1_14_G12") (pintype "bidirectional"))
    )
    (net (code "132") (name "unconnected-(U1-GPIO_AD_B1_15-PadJ14)") (class "Default")
      (node (ref "U1") (pin "J14") (pinfunction "GPIO_AD_B1_15_J14") (pintype "bidirectional"))
    )
    (net (code "133") (name "unconnected-(U1-GPIO_B0_00-PadD7)") (class "Default")
      (node (ref "U1") (pin "D7") (pinfunction "GPIO_B0_00_D7") (pintype "bidirectional"))
    )
    (net (code "134") (name "unconnected-(U1-GPIO_B0_01-PadE7)") (class "Default")
      (node (ref "U1") (pin "E7") (pinfunction "GPIO_B0_01_E7") (pintype "bidirectional"))
    )
    (net (code "135") (name "unconnected-(U1-GPIO_B0_02-PadE8)") (class "Default")
      (node (ref "U1") (pin "E8") (pinfunction "GPIO_B0_02_E8") (pintype "bidirectional"))
    )
    (net (code "136") (name "unconnected-(U1-GPIO_B0_03-PadD8)") (class "Default")
      (node (ref "U1") (pin "D8") (pinfunction "GPIO_B0_03_D8") (pintype "bidirectional"))
    )
    (net (code "137") (name "unconnected-(U1-GPIO_B0_04-PadC8)") (class "Default")
      (node (ref "U1") (pin "C8") (pinfunction "GPIO_B0_04_C8") (pintype "bidirectional"))
    )
    (net (code "138") (name "unconnected-(U1-GPIO_B0_05-PadB8)") (class "Default")
      (node (ref "U1") (pin "B8") (pinfunction "GPIO_B0_05_B8") (pintype "bidirectional"))
    )
    (net (code "139") (name "unconnected-(U1-GPIO_B0_06-PadA8)") (class "Default")
      (node (ref "U1") (pin "A8") (pinfunction "GPIO_B0_06_A8") (pintype "bidirectional"))
    )
    (net (code "140") (name "unconnected-(U1-GPIO_B0_07-PadA9)") (class "Default")
      (node (ref "U1") (pin "A9") (pinfunction "GPIO_B0_07_A9") (pintype "bidirectional"))
    )
    (net (code "141") (name "unconnected-(U1-GPIO_B0_08-PadB9)") (class "Default")
      (node (ref "U1") (pin "B9") (pinfunction "GPIO_B0_08_B9") (pintype "bidirectional"))
    )
    (net (code "142") (name "unconnected-(U1-GPIO_B0_09-PadC9)") (class "Default")
      (node (ref "U1") (pin "C9") (pinfunction "GPIO_B0_09_C9") (pintype "bidirectional"))
    )
    (net (code "143") (name "unconnected-(U1-GPIO_B0_10-PadD9)") (class "Default")
      (node (ref "U1") (pin "D9") (pinfunction "GPIO_B0_10_D9") (pintype "bidirectional"))
    )
    (net (code "144") (name "unconnected-(U1-GPIO_B0_11-PadA10)") (class "Default")
      (node (ref "U1") (pin "A10") (pinfunction "GPIO_B0_11_A10") (pintype "bidirectional"))
    )
    (net (code "145") (name "unconnected-(U1-GPIO_B0_12-PadC10)") (class "Default")
      (node (ref "U1") (pin "C10") (pinfunction "GPIO_B0_12_C10") (pintype "bidirectional"))
    )
    (net (code "146") (name "unconnected-(U1-GPIO_B0_13-PadD10)") (class "Default")
      (node (ref "U1") (pin "D10") (pinfunction "GPIO_B0_13_D10") (pintype "bidirectional"))
    )
    (net (code "147") (name "unconnected-(U1-GPIO_B0_14-PadE10)") (class "Default")
      (node (ref "U1") (pin "E10") (pinfunction "GPIO_B0_14_E10") (pintype "bidirectional"))
    )
    (net (code "148") (name "unconnected-(U1-GPIO_B0_15-PadE11)") (class "Default")
      (node (ref "U1") (pin "E11") (pinfunction "GPIO_B0_15_E11") (pintype "bidirectional"))
    )
    (net (code "149") (name "unconnected-(U1-GPIO_B1_00-PadA11)") (class "Default")
      (node (ref "U1") (pin "A11") (pinfunction "GPIO_B1_00_A11") (pintype "bidirectional"))
    )
    (net (code "150") (name "unconnected-(U1-GPIO_B1_01-PadB11)") (class "Default")
      (node (ref "U1") (pin "B11") (pinfunction "GPIO_B1_01_B11") (pintype "bidirectional"))
    )
    (net (code "151") (name "unconnected-(U1-GPIO_B1_02-PadC11)") (class "Default")
      (node (ref "U1") (pin "C11") (pinfunction "GPIO_B1_02_C11") (pintype "bidirectional"))
    )
    (net (code "152") (name "unconnected-(U1-GPIO_B1_03-PadD11)") (class "Default")
      (node (ref "U1") (pin "D11") (pinfunction "GPIO_B1_03_D11") (pintype "bidirectional"))
    )
    (net (code "153") (name "unconnected-(U1-GPIO_B1_04-PadE12)") (class "Default")
      (node (ref "U1") (pin "E12") (pinfunction "GPIO_B1_04_E12") (pintype "bidirectional"))
    )
    (net (code "154") (name "unconnected-(U1-GPIO_B1_05-PadD12)") (class "Default")
      (node (ref "U1") (pin "D12") (pinfunction "GPIO_B1_05_D12") (pintype "bidirectional"))
    )
    (net (code "155") (name "unconnected-(U1-GPIO_B1_06-PadC12)") (class "Default")
      (node (ref "U1") (pin "C12") (pinfunction "GPIO_B1_06_C12") (pintype "bidirectional"))
    )
    (net (code "156") (name "unconnected-(U1-GPIO_B1_07-PadB12)") (class "Default")
      (node (ref "U1") (pin "B12") (pinfunction "GPIO_B1_07_B12") (pintype "bidirectional"))
    )
    (net (code "157") (name "unconnected-(U1-GPIO_B1_08-PadA12)") (class "Default")
      (node (ref "U1") (pin "A12") (pinfunction "GPIO_B1_08_A12") (pintype "bidirectional"))
    )
    (net (code "158") (name "unconnected-(U1-GPIO_B1_09-PadA13)") (class "Default")
      (node (ref "U1") (pin "A13") (pinfunction "GPIO_B1_09_A13") (pintype "bidirectional"))
    )
    (net (code "159") (name "unconnected-(U1-GPIO_B1_10-PadB13)") (class "Default")
      (node (ref "U1") (pin "B13") (pinfunction "GPIO_B1_10_B13") (pintype "bidirectional"))
    )
    (net (code "160") (name "unconnected-(U1-GPIO_B1_11-PadC13)") (class "Default")
      (node (ref "U1") (pin "C13") (pinfunction "GPIO_B1_11_C13") (pintype "bidirectional"))
    )
    (net (code "161") (name "unconnected-(U1-GPIO_B1_12-PadD13)") (class "Default")
      (node (ref "U1") (pin "D13") (pinfunction "GPIO_B1_12_D13") (pintype "bidirectional"))
    )
    (net (code "162") (name "unconnected-(U1-GPIO_B1_13-PadD14)") (class "Default")
      (node (ref "U1") (pin "D14") (pinfunction "GPIO_B1_13_D14") (pintype "bidirectional"))
    )
    (net (code "163") (name "unconnected-(U1-GPIO_B1_14-PadC14)") (class "Default")
      (node (ref "U1") (pin "C14") (pinfunction "GPIO_B1_14_C14") (pintype "bidirectional"))
    )
    (net (code "164") (name "unconnected-(U1-GPIO_B1_15-PadB14)") (class "Default")
      (node (ref "U1") (pin "B14") (pinfunction "GPIO_B1_15_B14") (pintype "bidirectional"))
    )
    (net (code "165") (name "unconnected-(U1-POR_B-PadM7)") (class "Default")
      (node (ref "U1") (pin "M7") (pinfunction "POR_B_M7") (pintype "input"))
    )
    (net (code "166") (name "unconnected-(U1-RTC_XTALI-PadN9)") (class "Default")
      (node (ref "U1") (pin "N9") (pinfunction "RTC_XTALI_N9") (pintype "input"))
    )
    (net (code "167") (name "unconnected-(U1-RTC_XTALO-PadP9)") (class "Default")
      (node (ref "U1") (pin "P9") (pinfunction "RTC_XTALO_P9") (pintype "output"))
    )
    (net (code "168") (name "unconnected-(U1-TEST_MODE-PadK6)") (class "Default")
      (node (ref "U1") (pin "K6") (pinfunction "TEST_MODE_K6") (pintype "input"))
    )
    (net (code "169") (name "unconnected-(U1-WAKEUP-PadL6)") (class "Default")
      (node (ref "U1") (pin "L6") (pinfunction "WAKEUP_L6") (pintype "input"))
    )
  )
)
